# arduino_shield.net
KiCad netlist of a schematic drawn in EAGLE
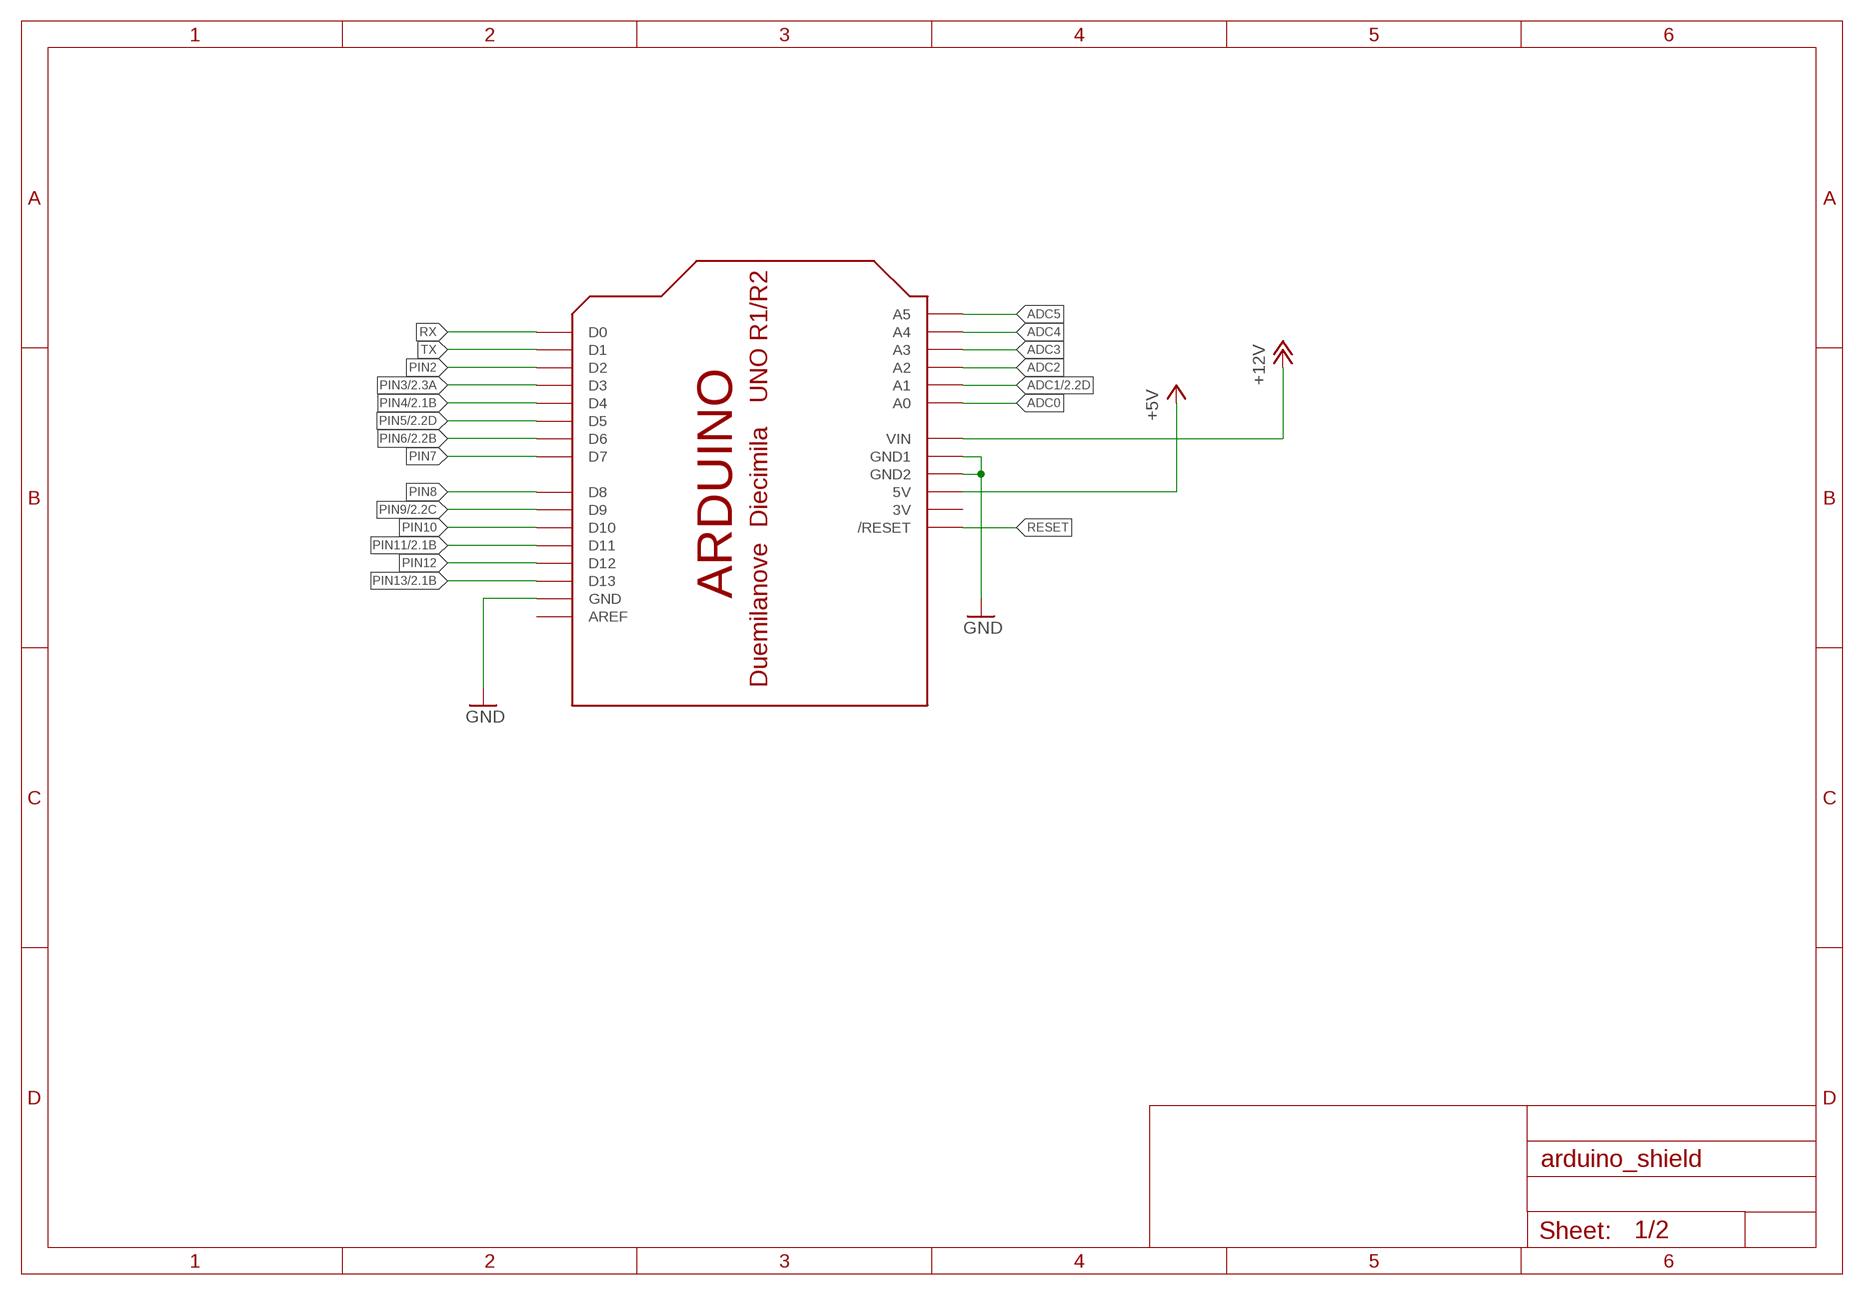
[diagram p0: schematic, sheet 1]
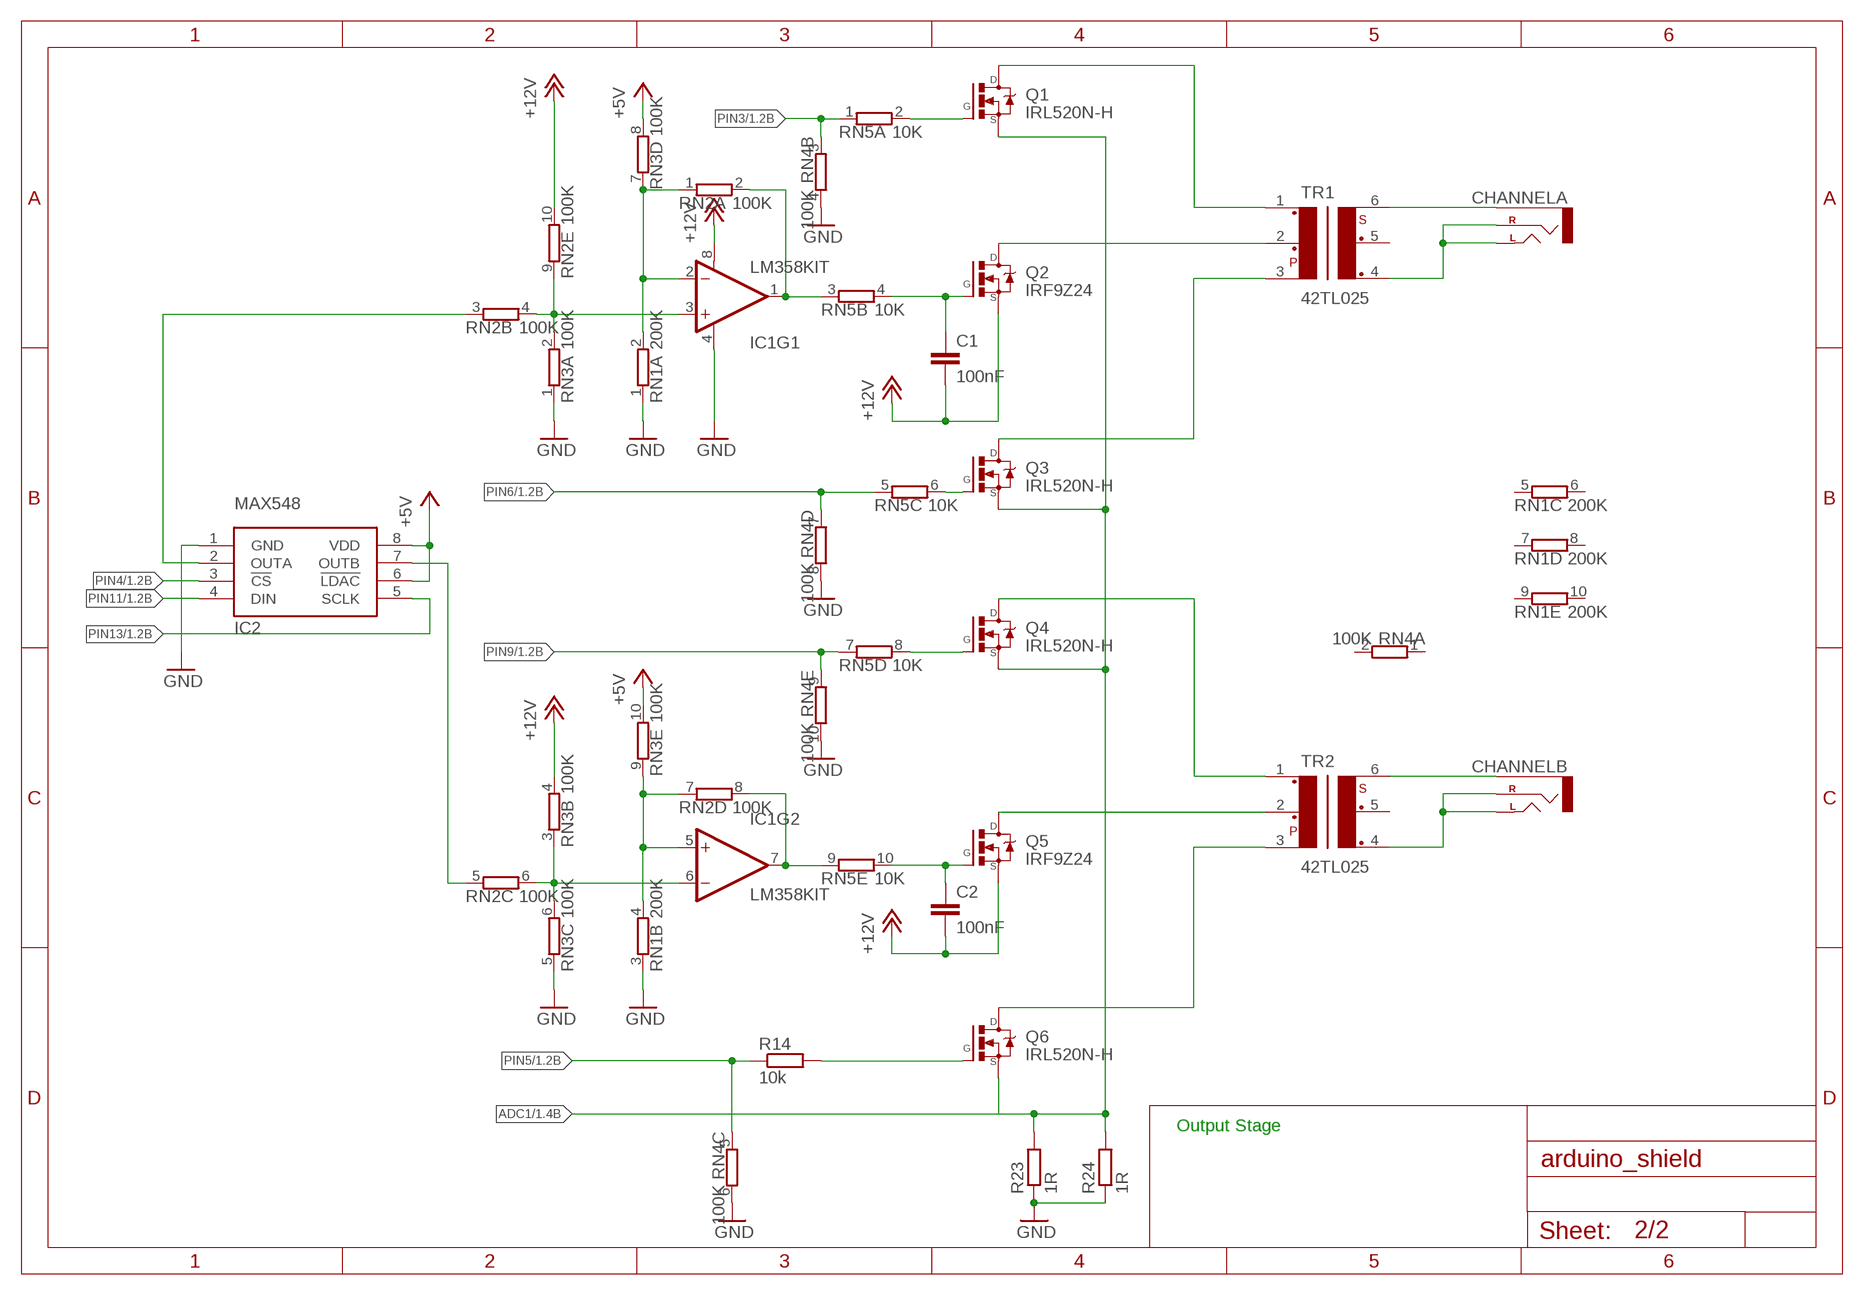
[diagram p1: schematic, sheet 2]

(export (version "E")
  (design (tool "Eeschema 10.0.6"))
  (components
    (comp (ref "C1")
      (value "100nF")
      (footprint "eagle-import:C2.5-2")
      (libsource (lib "eagle-import") (part "C2.5/2"))
    )
    (comp (ref "C2")
      (value "100nF")
      (footprint "eagle-import:C2.5-2")
      (libsource (lib "eagle-import") (part "C2.5/2"))
    )
    (comp (ref "CHANNELA")
      (value "AUDIO-JACK2.5MM")
      (footprint "eagle-import:STEREOJACK2.5MM_STEREOJACK2.5MM")
      (libsource (lib "eagle-import") (part "AUDIO-JACK2.5MM"))
    )
    (comp (ref "CHANNELB")
      (value "AUDIO-JACK2.5MM")
      (footprint "eagle-import:STEREOJACK2.5MM_STEREOJACK2.5MM")
      (libsource (lib "eagle-import") (part "AUDIO-JACK2.5MM"))
    )
    (comp (ref "IC1")
      (value "LM358KIT")
      (footprint "eagle-import:DIP08-KIT")
      (libsource (lib "eagle-import") (part "LM358KIT"))
    )
    (comp (ref "IC2")
      (value "MAX548")
      (footprint "eagle-import:DIL08")
      (libsource (lib "eagle-import") (part "MAX548"))
    )
    (comp (ref "Q1")
      (value "IRL520N-H")
      (footprint "eagle-import:TO220V")
      (libsource (lib "eagle-import") (part "IRL530N-V"))
    )
    (comp (ref "Q2")
      (value "IRF9Z24")
      (footprint "eagle-import:TO220V")
      (libsource (lib "eagle-import") (part "IRL530N-V"))
    )
    (comp (ref "Q3")
      (value "IRL520N-H")
      (footprint "eagle-import:TO220V")
      (libsource (lib "eagle-import") (part "IRL530N-V"))
    )
    (comp (ref "Q4")
      (value "IRL520N-H")
      (footprint "eagle-import:TO220V")
      (libsource (lib "eagle-import") (part "IRL530N-V"))
    )
    (comp (ref "Q5")
      (value "IRF9Z24")
      (footprint "eagle-import:TO220V")
      (libsource (lib "eagle-import") (part "IRL530N-V"))
    )
    (comp (ref "Q6")
      (value "IRL520N-H")
      (footprint "eagle-import:TO220V")
      (libsource (lib "eagle-import") (part "IRL530N-V"))
    )
    (comp (ref "R14")
      (value "10k")
      (footprint "eagle-import:R0805")
      (libsource (lib "eagle-import") (part "R"))
    )
    (comp (ref "R23")
      (value "1R")
      (footprint "eagle-import:R0805")
      (libsource (lib "eagle-import") (part "R"))
    )
    (comp (ref "R24")
      (value "1R")
      (footprint "eagle-import:R0805")
      (libsource (lib "eagle-import") (part "R"))
    )
    (comp (ref "RN1")
      (value "200K")
      (footprint "eagle-import:SIL10")
      (libsource (lib "eagle-import") (part "E5R"))
    )
    (comp (ref "RN2")
      (value "100K")
      (footprint "eagle-import:SIL10")
      (libsource (lib "eagle-import") (part "E5R"))
    )
    (comp (ref "RN3")
      (value "100K")
      (footprint "eagle-import:SIL10")
      (libsource (lib "eagle-import") (part "E5R"))
    )
    (comp (ref "RN4")
      (value "100K")
      (footprint "eagle-import:SIL10")
      (libsource (lib "eagle-import") (part "E5R"))
    )
    (comp (ref "RN5")
      (value "10K")
      (footprint "eagle-import:SIL10")
      (libsource (lib "eagle-import") (part "E5R"))
    )
    (comp (ref "TR1")
      (value "42TL025")
      (footprint "eagle-import:42TL")
      (libsource (lib "eagle-import") (part "42T?L025"))
    )
    (comp (ref "TR2")
      (value "42TL025")
      (footprint "eagle-import:42TL")
      (libsource (lib "eagle-import") (part "42T?L025"))
    )
    (comp (ref "GND")
      (value "ARDUINOUNO")
      (footprint "eagle-import:ARDUINO")
      (libsource (lib "eagle-import") (part "ARDUINOUNO"))
    )
  )
  (nets
    (net (code "1") (name "+5V") (class "Default")
      (node (ref "GND") (pin "5V") (pinfunction "5V_5V") (pintype "power_in"))
      (node (ref "IC2") (pin "6") (pinfunction "~{LDAC}_6") (pintype "bidirectional"))
      (node (ref "IC2") (pin "8") (pinfunction "VDD_8") (pintype "bidirectional"))
      (node (ref "RN3") (pin "10") (pinfunction "2_10") (pintype "passive"))
      (node (ref "RN3") (pin "8") (pinfunction "2_8") (pintype "passive"))
    )
    (net (code "2") (name "+12V") (class "Default")
      (node (ref "C1") (pin "2") (pinfunction "2_2") (pintype "passive"))
      (node (ref "C2") (pin "2") (pinfunction "2_2") (pintype "passive"))
      (node (ref "GND") (pin "VIN") (pinfunction "VIN_VIN") (pintype "power_in"))
      (node (ref "IC1") (pin "8") (pinfunction "V+_8") (pintype "power_in"))
      (node (ref "Q2") (pin "3") (pinfunction "S_3") (pintype "passive"))
      (node (ref "Q5") (pin "3") (pinfunction "S_3") (pintype "passive"))
      (node (ref "RN2") (pin "10") (pinfunction "2_10") (pintype "passive"))
      (node (ref "RN3") (pin "4") (pinfunction "2_4") (pintype "passive"))
    )
    (net (code "3") (name "3V") (class "Default")
      (node (ref "GND") (pin "3V") (pinfunction "3V_3V") (pintype "power_in"))
    )
    (net (code "4") (name "ADC0") (class "Default")
      (node (ref "GND") (pin "A0") (pinfunction "A0_A0") (pintype "bidirectional"))
    )
    (net (code "5") (name "ADC1") (class "Default")
      (node (ref "GND") (pin "A1") (pinfunction "A1_A1") (pintype "bidirectional"))
      (node (ref "Q1") (pin "3") (pinfunction "S_3") (pintype "passive"))
      (node (ref "Q3") (pin "3") (pinfunction "S_3") (pintype "passive"))
      (node (ref "Q4") (pin "3") (pinfunction "S_3") (pintype "passive"))
      (node (ref "Q6") (pin "3") (pinfunction "S_3") (pintype "passive"))
      (node (ref "R23") (pin "2") (pinfunction "2_2") (pintype "passive"))
      (node (ref "R24") (pin "2") (pinfunction "2_2") (pintype "passive"))
    )
    (net (code "6") (name "ADC2") (class "Default")
      (node (ref "GND") (pin "A2") (pinfunction "A2_A2") (pintype "bidirectional"))
    )
    (net (code "7") (name "ADC3") (class "Default")
      (node (ref "GND") (pin "A3") (pinfunction "A3_A3") (pintype "bidirectional"))
    )
    (net (code "8") (name "ADC4") (class "Default")
      (node (ref "GND") (pin "A4") (pinfunction "A4_A4") (pintype "bidirectional"))
    )
    (net (code "9") (name "ADC5") (class "Default")
      (node (ref "GND") (pin "A5") (pinfunction "A5_A5") (pintype "bidirectional"))
    )
    (net (code "10") (name "GND") (class "Default")
      (node (ref "GND") (pin "GND") (pinfunction "GND_GND") (pintype "power_in"))
      (node (ref "GND") (pin "GND1") (pinfunction "GND1_GND1") (pintype "power_in"))
      (node (ref "GND") (pin "GND2") (pinfunction "GND2_GND2") (pintype "power_in"))
      (node (ref "IC1") (pin "4") (pinfunction "V-_4") (pintype "power_in"))
      (node (ref "IC2") (pin "1") (pinfunction "GND_1") (pintype "bidirectional"))
      (node (ref "R23") (pin "1") (pinfunction "1_1") (pintype "passive"))
      (node (ref "R24") (pin "1") (pinfunction "1_1") (pintype "passive"))
      (node (ref "RN1") (pin "1") (pinfunction "1_1") (pintype "passive"))
      (node (ref "RN1") (pin "3") (pinfunction "1_3") (pintype "passive"))
      (node (ref "RN3") (pin "1") (pinfunction "1_1") (pintype "passive"))
      (node (ref "RN3") (pin "5") (pinfunction "1_5") (pintype "passive"))
      (node (ref "RN4") (pin "10") (pinfunction "2_10") (pintype "passive"))
      (node (ref "RN4") (pin "4") (pinfunction "2_4") (pintype "passive"))
      (node (ref "RN4") (pin "6") (pinfunction "2_6") (pintype "passive"))
      (node (ref "RN4") (pin "8") (pinfunction "2_8") (pintype "passive"))
    )
    (net (code "11") (name "Net-(CHANNELA-LEFT)") (class "Default")
      (node (ref "CHANNELA") (pin "SHIELD") (pinfunction "LEFT_SHIELD") (pintype "bidirectional"))
      (node (ref "CHANNELA") (pin "TIP") (pinfunction "RIGHT_TIP") (pintype "bidirectional"))
      (node (ref "TR1") (pin "4") (pinfunction "4_4") (pintype "passive"))
    )
    (net (code "12") (name "Net-(CHANNELA-SLEEVE)") (class "Default")
      (node (ref "CHANNELA") (pin "RING1") (pinfunction "SLEEVE_RING1") (pintype "bidirectional"))
      (node (ref "TR1") (pin "6") (pinfunction "6_6") (pintype "passive"))
    )
    (net (code "13") (name "Net-(CHANNELB-LEFT)") (class "Default")
      (node (ref "CHANNELB") (pin "SHIELD") (pinfunction "LEFT_SHIELD") (pintype "bidirectional"))
      (node (ref "CHANNELB") (pin "TIP") (pinfunction "RIGHT_TIP") (pintype "bidirectional"))
      (node (ref "TR2") (pin "4") (pinfunction "4_4") (pintype "passive"))
    )
    (net (code "14") (name "Net-(CHANNELB-SLEEVE)") (class "Default")
      (node (ref "CHANNELB") (pin "RING1") (pinfunction "SLEEVE_RING1") (pintype "bidirectional"))
      (node (ref "TR2") (pin "6") (pinfunction "6_6") (pintype "passive"))
    )
    (net (code "15") (name "Net-(IC1A-+IN)") (class "Default")
      (node (ref "IC1") (pin "3") (pinfunction "+IN_3") (pintype "input"))
      (node (ref "RN2") (pin "4") (pinfunction "2_4") (pintype "passive"))
      (node (ref "RN2") (pin "9") (pinfunction "1_9") (pintype "passive"))
      (node (ref "RN3") (pin "2") (pinfunction "2_2") (pintype "passive"))
    )
    (net (code "16") (name "Net-(IC1A--IN)") (class "Default")
      (node (ref "IC1") (pin "2") (pinfunction "-IN_2") (pintype "input"))
      (node (ref "RN1") (pin "2") (pinfunction "2_2") (pintype "passive"))
      (node (ref "RN2") (pin "1") (pinfunction "1_1") (pintype "passive"))
      (node (ref "RN3") (pin "7") (pinfunction "1_7") (pintype "passive"))
    )
    (net (code "17") (name "Net-(IC1A-OUT)") (class "Default")
      (node (ref "IC1") (pin "1") (pinfunction "OUT_1") (pintype "output"))
      (node (ref "RN2") (pin "2") (pinfunction "2_2") (pintype "passive"))
      (node (ref "RN5") (pin "3") (pinfunction "1_3") (pintype "passive"))
    )
    (net (code "18") (name "Net-(IC1B-+IN)") (class "Default")
      (node (ref "IC1") (pin "5") (pinfunction "+IN_5") (pintype "input"))
      (node (ref "RN1") (pin "4") (pinfunction "2_4") (pintype "passive"))
      (node (ref "RN2") (pin "7") (pinfunction "1_7") (pintype "passive"))
      (node (ref "RN3") (pin "9") (pinfunction "1_9") (pintype "passive"))
    )
    (net (code "19") (name "Net-(IC1B--IN)") (class "Default")
      (node (ref "IC1") (pin "6") (pinfunction "-IN_6") (pintype "input"))
      (node (ref "RN2") (pin "6") (pinfunction "2_6") (pintype "passive"))
      (node (ref "RN3") (pin "3") (pinfunction "1_3") (pintype "passive"))
      (node (ref "RN3") (pin "6") (pinfunction "2_6") (pintype "passive"))
    )
    (net (code "20") (name "Net-(IC1B-OUT)") (class "Default")
      (node (ref "IC1") (pin "7") (pinfunction "OUT_7") (pintype "output"))
      (node (ref "RN2") (pin "8") (pinfunction "2_8") (pintype "passive"))
      (node (ref "RN5") (pin "9") (pinfunction "1_9") (pintype "passive"))
    )
    (net (code "21") (name "Net-(IC2-OUTA)") (class "Default")
      (node (ref "IC2") (pin "2") (pinfunction "OUTA_2") (pintype "bidirectional"))
      (node (ref "RN2") (pin "3") (pinfunction "1_3") (pintype "passive"))
    )
    (net (code "22") (name "Net-(IC2-OUTB)") (class "Default")
      (node (ref "IC2") (pin "7") (pinfunction "OUTB_7") (pintype "bidirectional"))
      (node (ref "RN2") (pin "5") (pinfunction "1_5") (pintype "passive"))
    )
    (net (code "23") (name "Net-(Q1-D)") (class "Default")
      (node (ref "Q1") (pin "2") (pinfunction "D_2") (pintype "passive"))
      (node (ref "TR1") (pin "1") (pinfunction "1_1") (pintype "passive"))
    )
    (net (code "24") (name "Net-(Q1-G)") (class "Default")
      (node (ref "Q1") (pin "1") (pinfunction "G_1") (pintype "passive"))
      (node (ref "RN5") (pin "2") (pinfunction "2_2") (pintype "passive"))
    )
    (net (code "25") (name "Net-(Q2-D)") (class "Default")
      (node (ref "Q2") (pin "2") (pinfunction "D_2") (pintype "passive"))
      (node (ref "TR1") (pin "2") (pinfunction "2_2") (pintype "passive"))
    )
    (net (code "26") (name "Net-(Q2-G)") (class "Default")
      (node (ref "C1") (pin "1") (pinfunction "1_1") (pintype "passive"))
      (node (ref "Q2") (pin "1") (pinfunction "G_1") (pintype "passive"))
      (node (ref "RN5") (pin "4") (pinfunction "2_4") (pintype "passive"))
    )
    (net (code "27") (name "Net-(Q3-D)") (class "Default")
      (node (ref "Q3") (pin "2") (pinfunction "D_2") (pintype "passive"))
      (node (ref "TR1") (pin "3") (pinfunction "3_3") (pintype "passive"))
    )
    (net (code "28") (name "Net-(Q3-G)") (class "Default")
      (node (ref "Q3") (pin "1") (pinfunction "G_1") (pintype "passive"))
      (node (ref "RN5") (pin "6") (pinfunction "2_6") (pintype "passive"))
    )
    (net (code "29") (name "Net-(Q4-D)") (class "Default")
      (node (ref "Q4") (pin "2") (pinfunction "D_2") (pintype "passive"))
      (node (ref "TR2") (pin "1") (pinfunction "1_1") (pintype "passive"))
    )
    (net (code "30") (name "Net-(Q4-G)") (class "Default")
      (node (ref "Q4") (pin "1") (pinfunction "G_1") (pintype "passive"))
      (node (ref "RN5") (pin "8") (pinfunction "2_8") (pintype "passive"))
    )
    (net (code "31") (name "Net-(Q5-D)") (class "Default")
      (node (ref "Q5") (pin "2") (pinfunction "D_2") (pintype "passive"))
      (node (ref "TR2") (pin "2") (pinfunction "2_2") (pintype "passive"))
    )
    (net (code "32") (name "Net-(Q5-G)") (class "Default")
      (node (ref "C2") (pin "1") (pinfunction "1_1") (pintype "passive"))
      (node (ref "Q5") (pin "1") (pinfunction "G_1") (pintype "passive"))
      (node (ref "RN5") (pin "10") (pinfunction "2_10") (pintype "passive"))
    )
    (net (code "33") (name "Net-(Q6-D)") (class "Default")
      (node (ref "Q6") (pin "2") (pinfunction "D_2") (pintype "passive"))
      (node (ref "TR2") (pin "3") (pinfunction "3_3") (pintype "passive"))
    )
    (net (code "34") (name "Net-(Q6-G)") (class "Default")
      (node (ref "Q6") (pin "1") (pinfunction "G_1") (pintype "passive"))
      (node (ref "R14") (pin "2") (pinfunction "2_2") (pintype "passive"))
    )
    (net (code "35") (name "PIN2") (class "Default")
      (node (ref "GND") (pin "D2") (pinfunction "D2_D2") (pintype "bidirectional"))
    )
    (net (code "36") (name "PIN3") (class "Default")
      (node (ref "GND") (pin "D3") (pinfunction "D3_D3") (pintype "bidirectional"))
      (node (ref "RN4") (pin "3") (pinfunction "1_3") (pintype "passive"))
      (node (ref "RN5") (pin "1") (pinfunction "1_1") (pintype "passive"))
    )
    (net (code "37") (name "PIN4") (class "Default")
      (node (ref "GND") (pin "D4") (pinfunction "D4_D4") (pintype "bidirectional"))
      (node (ref "IC2") (pin "3") (pinfunction "~{CS}_3") (pintype "bidirectional"))
    )
    (net (code "38") (name "PIN5") (class "Default")
      (node (ref "GND") (pin "D5") (pinfunction "D5_D5") (pintype "bidirectional"))
      (node (ref "R14") (pin "1") (pinfunction "1_1") (pintype "passive"))
      (node (ref "RN4") (pin "5") (pinfunction "1_5") (pintype "passive"))
    )
    (net (code "39") (name "PIN6") (class "Default")
      (node (ref "GND") (pin "D6") (pinfunction "D6_D6") (pintype "bidirectional"))
      (node (ref "RN4") (pin "7") (pinfunction "1_7") (pintype "passive"))
      (node (ref "RN5") (pin "5") (pinfunction "1_5") (pintype "passive"))
    )
    (net (code "40") (name "PIN7") (class "Default")
      (node (ref "GND") (pin "D7") (pinfunction "D7_D7") (pintype "bidirectional"))
    )
    (net (code "41") (name "PIN8") (class "Default")
      (node (ref "GND") (pin "D8") (pinfunction "D8_D8") (pintype "bidirectional"))
    )
    (net (code "42") (name "PIN9") (class "Default")
      (node (ref "GND") (pin "D9") (pinfunction "D9_D9") (pintype "bidirectional"))
      (node (ref "RN4") (pin "9") (pinfunction "1_9") (pintype "passive"))
      (node (ref "RN5") (pin "7") (pinfunction "1_7") (pintype "passive"))
    )
    (net (code "43") (name "PIN10") (class "Default")
      (node (ref "GND") (pin "D10") (pinfunction "D10_D10") (pintype "bidirectional"))
    )
    (net (code "44") (name "PIN11") (class "Default")
      (node (ref "GND") (pin "D11") (pinfunction "D11_D11") (pintype "bidirectional"))
      (node (ref "IC2") (pin "4") (pinfunction "DIN_4") (pintype "bidirectional"))
    )
    (net (code "45") (name "PIN12") (class "Default")
      (node (ref "GND") (pin "D12") (pinfunction "D12_D12") (pintype "bidirectional"))
    )
    (net (code "46") (name "PIN13") (class "Default")
      (node (ref "GND") (pin "D13") (pinfunction "D13_D13") (pintype "bidirectional"))
      (node (ref "IC2") (pin "5") (pinfunction "SCLK_5") (pintype "bidirectional"))
    )
    (net (code "47") (name "RESET") (class "Default")
      (node (ref "GND") (pin "RESET") (pinfunction "/RESET_RESET") (pintype "bidirectional"))
    )
    (net (code "48") (name "RX") (class "Default")
      (node (ref "GND") (pin "D0") (pinfunction "D0_D0") (pintype "bidirectional"))
    )
    (net (code "49") (name "TX") (class "Default")
      (node (ref "GND") (pin "D1") (pinfunction "D1_D1") (pintype "bidirectional"))
    )
    (net (code "50") (name "unconnected-(GND-PadAREF)") (class "Default")
      (node (ref "GND") (pin "AREF") (pinfunction "AREF_AREF") (pintype "bidirectional"))
    )
    (net (code "51") (name "unconnected-(RN1C-1-Pad5)") (class "Default")
      (node (ref "RN1") (pin "5") (pinfunction "1_5") (pintype "passive"))
    )
    (net (code "52") (name "unconnected-(RN1C-2-Pad6)") (class "Default")
      (node (ref "RN1") (pin "6") (pinfunction "2_6") (pintype "passive"))
    )
    (net (code "53") (name "unconnected-(RN1D-1-Pad7)") (class "Default")
      (node (ref "RN1") (pin "7") (pinfunction "1_7") (pintype "passive"))
    )
    (net (code "54") (name "unconnected-(RN1D-2-Pad8)") (class "Default")
      (node (ref "RN1") (pin "8") (pinfunction "2_8") (pintype "passive"))
    )
    (net (code "55") (name "unconnected-(RN1E-1-Pad9)") (class "Default")
      (node (ref "RN1") (pin "9") (pinfunction "1_9") (pintype "passive"))
    )
    (net (code "56") (name "unconnected-(RN1E-2-Pad10)") (class "Default")
      (node (ref "RN1") (pin "10") (pinfunction "2_10") (pintype "passive"))
    )
    (net (code "57") (name "unconnected-(RN4-Pad1)") (class "Default")
      (node (ref "RN4") (pin "1") (pinfunction "1_1") (pintype "passive"))
    )
    (net (code "58") (name "unconnected-(RN4-Pad2)") (class "Default")
      (node (ref "RN4") (pin "2") (pinfunction "2_2") (pintype "passive"))
    )
    (net (code "59") (name "unconnected-(TR1-Pad5)") (class "Default")
      (node (ref "TR1") (pin "5") (pinfunction "5_5") (pintype "passive"))
    )
    (net (code "60") (name "unconnected-(TR2-Pad5)") (class "Default")
      (node (ref "TR2") (pin "5") (pinfunction "5_5") (pintype "passive"))
    )
  )
)
